# Battery_Protection_Board.net
KiCad netlist of a schematic drawn in EAGLE
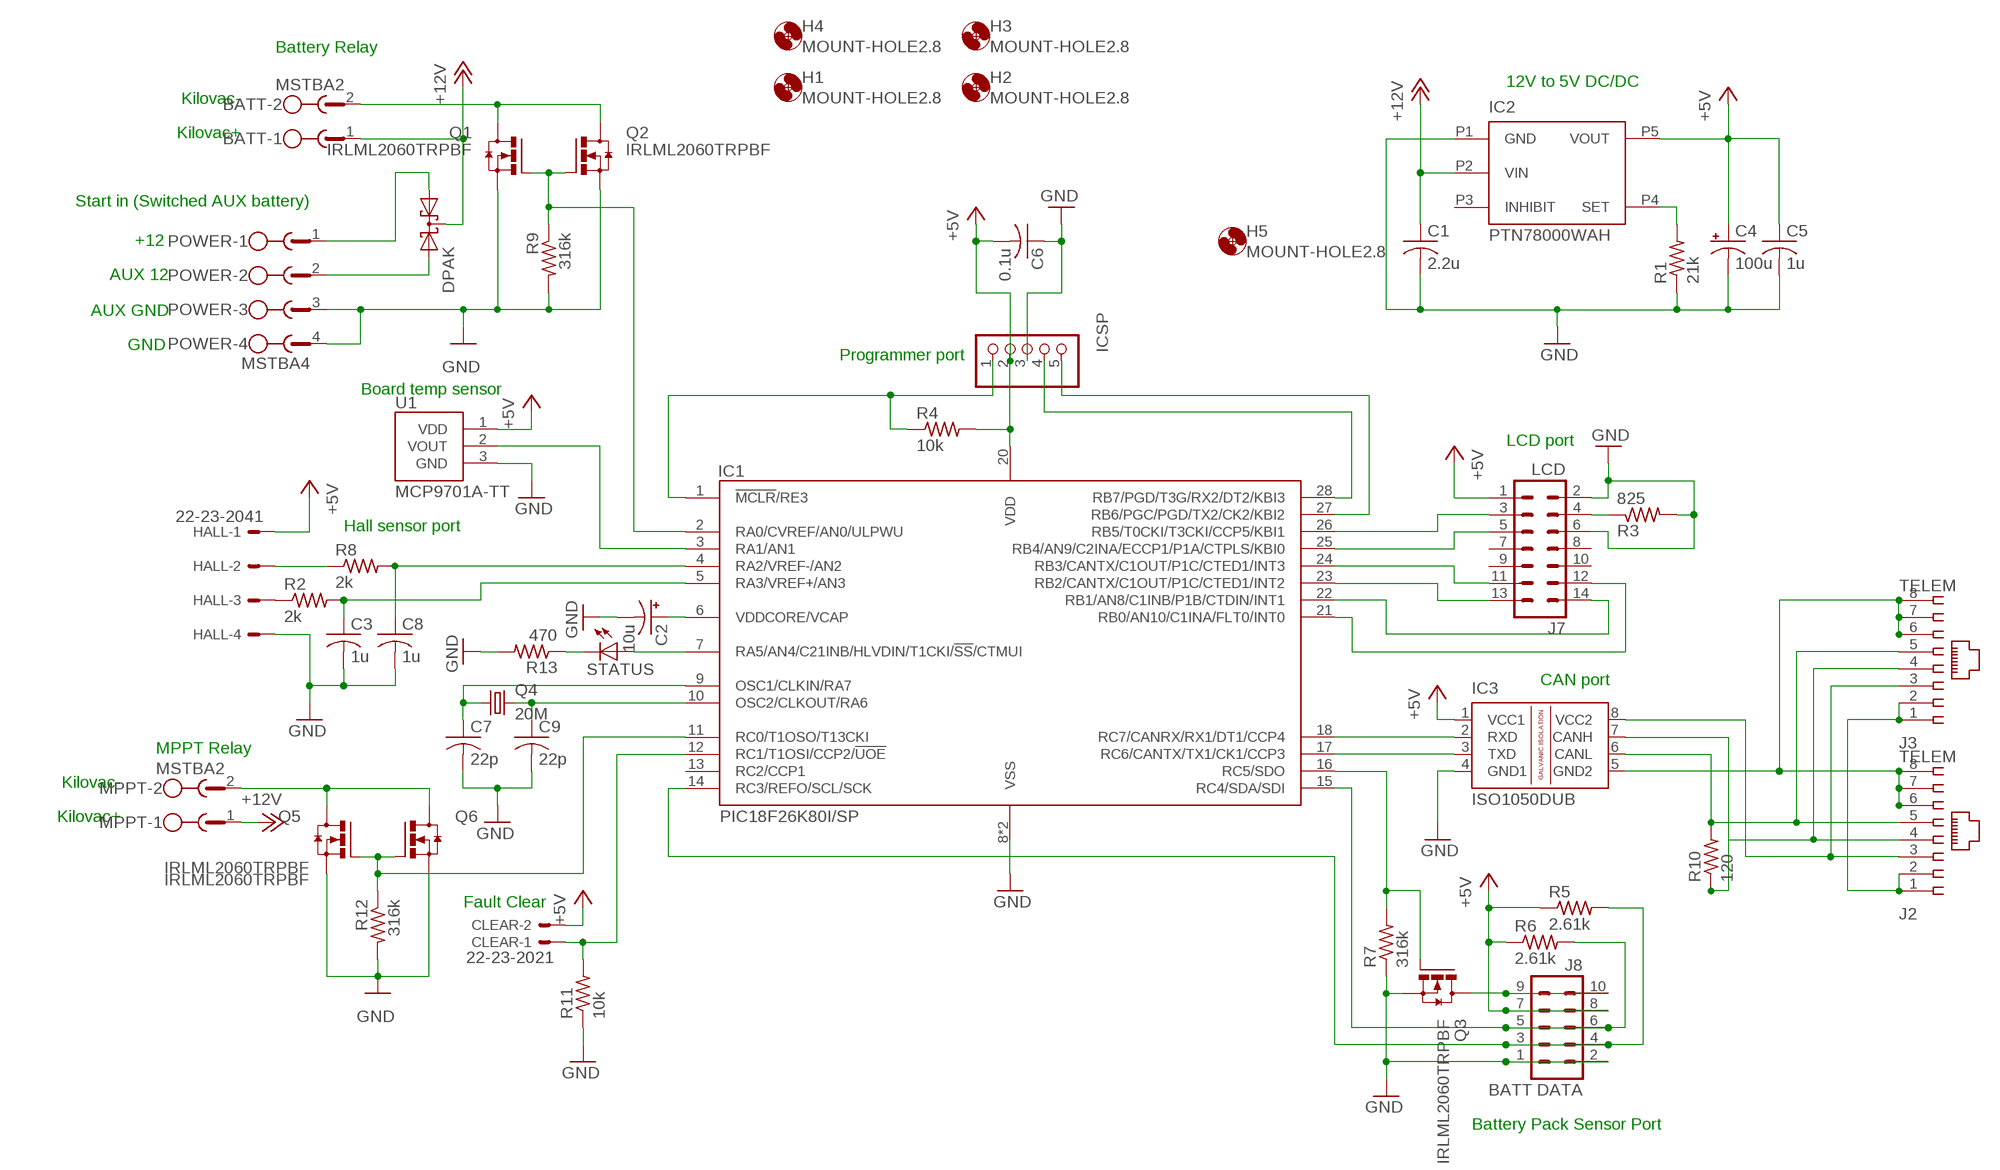
[diagram p0: schematic, sheet 1]

(export (version "E")
  (design (tool "Eeschema 10.0.6"))
  (components
    (comp (ref "BATT")
      (value "MSTBA2")
      (footprint "eagle-import:MSTBA2")
      (fields (field (name "MF") "FARNELL") (field (name "MPN") "1757242"))
      (libsource (lib "eagle-import") (part "MSTBA2"))
    )
    (comp (ref "C1")
      (value "2.2u")
      (footprint "eagle-import:C1206")
      (libsource (lib "eagle-import") (part "C-USC1206"))
    )
    (comp (ref "C2")
      (value "10u")
      (footprint "eagle-import:TT2D4")
      (libsource (lib "eagle-import") (part "CPOL-USTT2D4"))
    )
    (comp (ref "C3")
      (value "1u")
      (footprint "eagle-import:C0805")
      (libsource (lib "eagle-import") (part "C-USC0805"))
    )
    (comp (ref "C4")
      (value "100u")
      (footprint "eagle-import:SMC_D")
      (libsource (lib "eagle-import") (part "CPOL-USSMCD"))
    )
    (comp (ref "C5")
      (value "1u")
      (footprint "eagle-import:C0805")
      (libsource (lib "eagle-import") (part "C-USC0805"))
    )
    (comp (ref "C6")
      (value "0.1u")
      (footprint "eagle-import:C0805")
      (libsource (lib "eagle-import") (part "C-USC0805"))
    )
    (comp (ref "C7")
      (value "22p")
      (footprint "eagle-import:C0805")
      (libsource (lib "eagle-import") (part "C-USC0805"))
    )
    (comp (ref "C8")
      (value "1u")
      (footprint "eagle-import:C0805")
      (libsource (lib "eagle-import") (part "C-USC0805"))
    )
    (comp (ref "C9")
      (value "22p")
      (footprint "eagle-import:C0805")
      (libsource (lib "eagle-import") (part "C-USC0805"))
    )
    (comp (ref "CLEAR")
      (value "22-23-2021")
      (footprint "eagle-import:22-23-2021")
      (fields (field (name "MF") "MOLEX"))
      (libsource (lib "eagle-import") (part "22-23-2021"))
    )
    (comp (ref "DPAK")
      (value "DIODE_2SCHOTTKY-DPAK")
      (footprint "eagle-import:DPAK")
      (libsource (lib "eagle-import") (part "DIODE_2SCHOTTKY-DPAK"))
    )
    (comp (ref "H1")
      (value "MOUNT-HOLE2.8")
      (footprint "eagle-import:2,8")
      (libsource (lib "eagle-import") (part "MOUNT-HOLE2.8"))
    )
    (comp (ref "H2")
      (value "MOUNT-HOLE2.8")
      (footprint "eagle-import:2,8")
      (libsource (lib "eagle-import") (part "MOUNT-HOLE2.8"))
    )
    (comp (ref "H3")
      (value "MOUNT-HOLE2.8")
      (footprint "eagle-import:2,8")
      (libsource (lib "eagle-import") (part "MOUNT-HOLE2.8"))
    )
    (comp (ref "H4")
      (value "MOUNT-HOLE2.8")
      (footprint "eagle-import:2,8")
      (libsource (lib "eagle-import") (part "MOUNT-HOLE2.8"))
    )
    (comp (ref "H5")
      (value "MOUNT-HOLE2.8")
      (footprint "eagle-import:2,8")
      (libsource (lib "eagle-import") (part "MOUNT-HOLE2.8"))
    )
    (comp (ref "HALL")
      (value "22-23-2041")
      (footprint "eagle-import:22-23-2041")
      (fields (field (name "MF") "MOLEX"))
      (libsource (lib "eagle-import") (part "22-23-2041"))
    )
    (comp (ref "IC1")
      (value "PIC18F26K80I/SP")
      (footprint "eagle-import:DIL28_3")
      (libsource (lib "eagle-import") (part "PIC18F26K80I/SP"))
    )
    (comp (ref "IC2")
      (value "PTN78000WAH")
      (footprint "eagle-import:PTN78000")
      (libsource (lib "eagle-import") (part "PTN78000WAH"))
    )
    (comp (ref "IC3")
      (value "ISO1050DUB")
      (footprint "eagle-import:DUB-R-PDSO-G8")
      (fields (field (name "MPN") "ISO1050DUBR"))
      (libsource (lib "eagle-import") (part "ISO1050DUB"))
    )
    (comp (ref "ICSP")
      (value "ICD")
      (footprint "eagle-import:1X05")
      (libsource (lib "eagle-import") (part "PINHD-1X5"))
    )
    (comp (ref "J2")
      (value "TELEM")
      (footprint "eagle-import:215877-7")
      (libsource (lib "eagle-import") (part "215877-7"))
    )
    (comp (ref "J3")
      (value "TELEM")
      (footprint "eagle-import:215877-7")
      (libsource (lib "eagle-import") (part "215877-7"))
    )
    (comp (ref "J7")
      (value "LCD")
      (footprint "eagle-import:ML14")
      (libsource (lib "eagle-import") (part "ML14"))
    )
    (comp (ref "J8")
      (value "BATT DATA")
      (footprint "eagle-import:ML10")
      (libsource (lib "eagle-import") (part "ML10"))
    )
    (comp (ref "MPPT")
      (value "MSTBA2")
      (footprint "eagle-import:MSTBA2")
      (fields (field (name "MF") "FARNELL") (field (name "MPN") "1757242"))
      (libsource (lib "eagle-import") (part "MSTBA2"))
    )
    (comp (ref "POWER")
      (value "MSTBA4")
      (footprint "eagle-import:MSTBA4")
      (fields (field (name "MF") "FARNELL") (field (name "MPN") "1757268"))
      (libsource (lib "eagle-import") (part "MSTBA4"))
    )
    (comp (ref "Q1")
      (value "IRLML2060TRPBF")
      (footprint "eagle-import:SOT23")
      (libsource (lib "eagle-import") (part "IRLML2060TRPBF"))
    )
    (comp (ref "Q2")
      (value "IRLML2060TRPBF")
      (footprint "eagle-import:SOT23")
      (libsource (lib "eagle-import") (part "IRLML2060TRPBF"))
    )
    (comp (ref "Q3")
      (value "IRLML2060TRPBF")
      (footprint "eagle-import:SOT23")
      (libsource (lib "eagle-import") (part "IRLML2060TRPBF"))
    )
    (comp (ref "Q4")
      (value "20M")
      (footprint "eagle-import:HC49_S")
      (libsource (lib "eagle-import") (part "CRYSTALHC49S"))
    )
    (comp (ref "Q5")
      (value "IRLML2060TRPBF")
      (footprint "eagle-import:SOT23")
      (libsource (lib "eagle-import") (part "IRLML2060TRPBF"))
    )
    (comp (ref "Q6")
      (value "IRLML2060TRPBF")
      (footprint "eagle-import:SOT23")
      (libsource (lib "eagle-import") (part "IRLML2060TRPBF"))
    )
    (comp (ref "R1")
      (value "21k")
      (footprint "eagle-import:R0805")
      (libsource (lib "eagle-import") (part "rcl_R-US_R0805"))
    )
    (comp (ref "R2")
      (value "2k")
      (footprint "eagle-import:R0805")
      (libsource (lib "eagle-import") (part "rcl_R-US_R0805"))
    )
    (comp (ref "R3")
      (value "825")
      (footprint "eagle-import:R0805")
      (libsource (lib "eagle-import") (part "rcl_R-US_R0805"))
    )
    (comp (ref "R4")
      (value "10k")
      (footprint "eagle-import:R0805")
      (libsource (lib "eagle-import") (part "rcl_R-US_R0805"))
    )
    (comp (ref "R5")
      (value "2.61k")
      (footprint "eagle-import:R0805")
      (libsource (lib "eagle-import") (part "rcl_R-US_R0805"))
    )
    (comp (ref "R6")
      (value "2.61k")
      (footprint "eagle-import:R0805")
      (libsource (lib "eagle-import") (part "rcl_R-US_R0805"))
    )
    (comp (ref "R7")
      (value "316k")
      (footprint "eagle-import:R0805")
      (libsource (lib "eagle-import") (part "rcl_R-US_R0805"))
    )
    (comp (ref "R8")
      (value "2k")
      (footprint "eagle-import:R0805")
      (libsource (lib "eagle-import") (part "rcl_R-US_R0805"))
    )
    (comp (ref "R9")
      (value "316k")
      (footprint "eagle-import:R0805")
      (libsource (lib "eagle-import") (part "rcl_R-US_R0805"))
    )
    (comp (ref "R10")
      (value "120")
      (footprint "eagle-import:0207_7")
      (libsource (lib "eagle-import") (part "R-US_0207/7"))
    )
    (comp (ref "R11")
      (value "10k")
      (footprint "eagle-import:R0805")
      (libsource (lib "eagle-import") (part "rcl_R-US_R0805"))
    )
    (comp (ref "R12")
      (value "316k")
      (footprint "eagle-import:R0805")
      (libsource (lib "eagle-import") (part "rcl_R-US_R0805"))
    )
    (comp (ref "R13")
      (value "470")
      (footprint "eagle-import:R0805")
      (libsource (lib "eagle-import") (part "rcl_R-US_R0805"))
    )
    (comp (ref "STATUS")
      (value "LED5MM")
      (footprint "eagle-import:LED5MM")
      (libsource (lib "eagle-import") (part "LED5MM"))
    )
    (comp (ref "U1")
      (value "MCP9701A-TT")
      (footprint "eagle-import:SOT23")
      (libsource (lib "eagle-import") (part "MCP9701A-TT"))
    )
  )
  (nets
    (net (code "1") (name "+5V") (class "Default")
      (node (ref "C4") (pin "+") (pinfunction "+_+") (pintype "passive"))
      (node (ref "C5") (pin "1") (pinfunction "1_1") (pintype "passive"))
      (node (ref "C6") (pin "2") (pinfunction "2_2") (pintype "passive"))
      (node (ref "CLEAR") (pin "2") (pinfunction "S_2") (pintype "passive"))
      (node (ref "HALL") (pin "1") (pinfunction "S_1") (pintype "passive"))
      (node (ref "IC1") (pin "20") (pinfunction "VDD_20") (pintype "power_in"))
      (node (ref "IC2") (pin "P5") (pinfunction "VOUT_P5") (pintype "power_in"))
      (node (ref "IC3") (pin "1") (pinfunction "VCC1_1") (pintype "input"))
      (node (ref "ICSP") (pin "2") (pinfunction "2_2") (pintype "passive"))
      (node (ref "J7") (pin "1") (pinfunction "1_1") (pintype "passive"))
      (node (ref "J8") (pin "7") (pinfunction "7_7") (pintype "passive"))
      (node (ref "J8") (pin "8") (pinfunction "8_8") (pintype "passive"))
      (node (ref "R4") (pin "2") (pinfunction "2_2") (pintype "passive"))
      (node (ref "R5") (pin "1") (pinfunction "1_1") (pintype "passive"))
      (node (ref "R6") (pin "1") (pinfunction "1_1") (pintype "passive"))
      (node (ref "U1") (pin "1") (pinfunction "VDD_1") (pintype "power_in"))
    )
    (net (code "2") (name "+12V") (class "Default")
      (node (ref "BATT") (pin "1") (pinfunction "1_1") (pintype "passive"))
      (node (ref "C1") (pin "1") (pinfunction "1_1") (pintype "passive"))
      (node (ref "DPAK") (pin "3") (pinfunction "C_3") (pintype "passive"))
      (node (ref "IC2") (pin "P2") (pinfunction "VIN_P2") (pintype "power_in"))
      (node (ref "MPPT") (pin "1") (pinfunction "1_1") (pintype "passive"))
    )
    (net (code "3") (name "GND") (class "Default")
      (node (ref "C1") (pin "2") (pinfunction "2_2") (pintype "passive"))
      (node (ref "C2") (pin "-") (pinfunction "-_-") (pintype "passive"))
      (node (ref "C3") (pin "2") (pinfunction "2_2") (pintype "passive"))
      (node (ref "C4") (pin "-") (pinfunction "-_-") (pintype "passive"))
      (node (ref "C5") (pin "2") (pinfunction "2_2") (pintype "passive"))
      (node (ref "C6") (pin "1") (pinfunction "1_1") (pintype "passive"))
      (node (ref "C7") (pin "2") (pinfunction "2_2") (pintype "passive"))
      (node (ref "C8") (pin "2") (pinfunction "2_2") (pintype "passive"))
      (node (ref "C9") (pin "2") (pinfunction "2_2") (pintype "passive"))
      (node (ref "HALL") (pin "4") (pinfunction "S_4") (pintype "passive"))
      (node (ref "IC1") (pin "19") (pinfunction "VSS_19") (pintype "power_in"))
      (node (ref "IC1") (pin "8") (pinfunction "VSS_8") (pintype "power_in"))
      (node (ref "IC2") (pin "P1") (pinfunction "GND_P1") (pintype "power_in"))
      (node (ref "IC3") (pin "4") (pinfunction "GND1_4") (pintype "input"))
      (node (ref "ICSP") (pin "3") (pinfunction "3_3") (pintype "passive"))
      (node (ref "J7") (pin "2") (pinfunction "2_2") (pintype "passive"))
      (node (ref "J7") (pin "6") (pinfunction "6_6") (pintype "passive"))
      (node (ref "J8") (pin "1") (pinfunction "1_1") (pintype "passive"))
      (node (ref "J8") (pin "2") (pinfunction "2_2") (pintype "passive"))
      (node (ref "POWER") (pin "3") (pinfunction "1_3") (pintype "passive"))
      (node (ref "POWER") (pin "4") (pinfunction "1_4") (pintype "passive"))
      (node (ref "Q1") (pin "2") (pinfunction "S_2") (pintype "passive"))
      (node (ref "Q2") (pin "2") (pinfunction "S_2") (pintype "passive"))
      (node (ref "Q3") (pin "2") (pinfunction "S_2") (pintype "passive"))
      (node (ref "Q5") (pin "2") (pinfunction "S_2") (pintype "passive"))
      (node (ref "Q6") (pin "2") (pinfunction "S_2") (pintype "passive"))
      (node (ref "R1") (pin "1") (pinfunction "1_1") (pintype "passive"))
      (node (ref "R11") (pin "1") (pinfunction "1_1") (pintype "passive"))
      (node (ref "R12") (pin "2") (pinfunction "2_2") (pintype "passive"))
      (node (ref "R13") (pin "2") (pinfunction "2_2") (pintype "passive"))
      (node (ref "R3") (pin "2") (pinfunction "2_2") (pintype "passive"))
      (node (ref "R7") (pin "1") (pinfunction "1_1") (pintype "passive"))
      (node (ref "R9") (pin "2") (pinfunction "2_2") (pintype "passive"))
      (node (ref "U1") (pin "3") (pinfunction "GND_3") (pintype "power_in"))
    )
    (net (code "4") (name "Net-(BATTB-1)") (class "Default")
      (node (ref "BATT") (pin "2") (pinfunction "1_2") (pintype "passive"))
      (node (ref "Q1") (pin "3") (pinfunction "D_3") (pintype "passive"))
      (node (ref "Q2") (pin "3") (pinfunction "D_3") (pintype "passive"))
    )
    (net (code "5") (name "Net-(CLEARA-S)") (class "Default")
      (node (ref "CLEAR") (pin "1") (pinfunction "S_1") (pintype "passive"))
      (node (ref "IC1") (pin "12") (pinfunction "RC1/T1OSI/CCP2/~{UOE}_12") (pintype "bidirectional"))
      (node (ref "R11") (pin "2") (pinfunction "2_2") (pintype "passive"))
    )
    (net (code "6") (name "Net-(DPAK-A1)") (class "Default")
      (node (ref "DPAK") (pin "1") (pinfunction "A1_1") (pintype "passive"))
      (node (ref "POWER") (pin "1") (pinfunction "1_1") (pintype "passive"))
    )
    (net (code "7") (name "Net-(DPAK-A2)") (class "Default")
      (node (ref "DPAK") (pin "2") (pinfunction "A2_2") (pintype "passive"))
      (node (ref "POWER") (pin "2") (pinfunction "1_2") (pintype "passive"))
    )
    (net (code "8") (name "Net-(HALLB-S)") (class "Default")
      (node (ref "HALL") (pin "2") (pinfunction "S_2") (pintype "passive"))
      (node (ref "R8") (pin "1") (pinfunction "1_1") (pintype "passive"))
    )
    (net (code "9") (name "Net-(HALLC-S)") (class "Default")
      (node (ref "HALL") (pin "3") (pinfunction "S_3") (pintype "passive"))
      (node (ref "R2") (pin "1") (pinfunction "1_1") (pintype "passive"))
    )
    (net (code "10") (name "Net-(IC1-OSC1{slash}CLKIN{slash}RA7)") (class "Default")
      (node (ref "C7") (pin "1") (pinfunction "1_1") (pintype "passive"))
      (node (ref "IC1") (pin "9") (pinfunction "OSC1/CLKIN/RA7_9") (pintype "bidirectional"))
      (node (ref "Q4") (pin "1") (pinfunction "1_1") (pintype "passive"))
    )
    (net (code "11") (name "Net-(IC1-OSC2{slash}CLKOUT{slash}RA6)") (class "Default")
      (node (ref "C9") (pin "1") (pinfunction "1_1") (pintype "passive"))
      (node (ref "IC1") (pin "10") (pinfunction "OSC2/CLKOUT/RA6_10") (pintype "bidirectional"))
      (node (ref "Q4") (pin "2") (pinfunction "2_2") (pintype "passive"))
    )
    (net (code "12") (name "Net-(IC1-RA0{slash}CVREF{slash}AN0{slash}ULPWU)") (class "Default")
      (node (ref "IC1") (pin "2") (pinfunction "RA0/CVREF/AN0/ULPWU_2") (pintype "bidirectional"))
      (node (ref "Q1") (pin "1") (pinfunction "G_1") (pintype "passive"))
      (node (ref "Q2") (pin "1") (pinfunction "G_1") (pintype "passive"))
      (node (ref "R9") (pin "1") (pinfunction "1_1") (pintype "passive"))
    )
    (net (code "13") (name "Net-(IC1-RA1{slash}AN1)") (class "Default")
      (node (ref "IC1") (pin "3") (pinfunction "RA1/AN1_3") (pintype "bidirectional"))
      (node (ref "U1") (pin "2") (pinfunction "VOUT_2") (pintype "output"))
    )
    (net (code "14") (name "Net-(IC1-RA2{slash}VREF-{slash}AN2)") (class "Default")
      (node (ref "C8") (pin "1") (pinfunction "1_1") (pintype "passive"))
      (node (ref "IC1") (pin "4") (pinfunction "RA2/VREF-/AN2_4") (pintype "bidirectional"))
      (node (ref "R8") (pin "2") (pinfunction "2_2") (pintype "passive"))
    )
    (net (code "15") (name "Net-(IC1-RA3{slash}VREF+{slash}AN3)") (class "Default")
      (node (ref "C3") (pin "1") (pinfunction "1_1") (pintype "passive"))
      (node (ref "IC1") (pin "5") (pinfunction "RA3/VREF+/AN3_5") (pintype "bidirectional"))
      (node (ref "R2") (pin "2") (pinfunction "2_2") (pintype "passive"))
    )
    (net (code "16") (name "Net-(IC1-RA5{slash}AN4{slash}C21INB{slash}HLVDIN{slash}T1CKI{slash}~{SS}{slash}CTMUI)") (class "Default")
      (node (ref "IC1") (pin "7") (pinfunction "RA5/AN4/C21INB/HLVDIN/T1CKI/~{SS}/CTMUI_7") (pintype "bidirectional"))
      (node (ref "STATUS") (pin "A") (pinfunction "A_A") (pintype "passive"))
    )
    (net (code "17") (name "Net-(IC1-RB0{slash}AN10{slash}C1INA{slash}FLT0{slash}INT0)") (class "Default")
      (node (ref "IC1") (pin "21") (pinfunction "RB0/AN10/C1INA/FLT0/INT0_21") (pintype "bidirectional"))
      (node (ref "J7") (pin "12") (pinfunction "12_12") (pintype "passive"))
    )
    (net (code "18") (name "Net-(IC1-RB1{slash}AN8{slash}C1INB{slash}P1B{slash}CTDIN{slash}INT1)") (class "Default")
      (node (ref "IC1") (pin "22") (pinfunction "RB1/AN8/C1INB/P1B/CTDIN/INT1_22") (pintype "bidirectional"))
      (node (ref "J7") (pin "14") (pinfunction "14_14") (pintype "passive"))
    )
    (net (code "19") (name "Net-(IC1-RB2{slash}CANTX{slash}C1OUT{slash}P1C{slash}CTED1{slash}INT2)") (class "Default")
      (node (ref "IC1") (pin "23") (pinfunction "RB2/CANTX/C1OUT/P1C/CTED1/INT2_23") (pintype "bidirectional"))
      (node (ref "J7") (pin "13") (pinfunction "13_13") (pintype "passive"))
    )
    (net (code "20") (name "Net-(IC1-RB3{slash}CANTX{slash}C1OUT{slash}P1C{slash}CTED1{slash}INT3)") (class "Default")
      (node (ref "IC1") (pin "24") (pinfunction "RB3/CANTX/C1OUT/P1C/CTED1/INT3_24") (pintype "bidirectional"))
      (node (ref "J7") (pin "11") (pinfunction "11_11") (pintype "passive"))
    )
    (net (code "21") (name "Net-(IC1-RB4{slash}AN9{slash}C2INA{slash}ECCP1{slash}P1A{slash}CTPLS{slash}KBI0)") (class "Default")
      (node (ref "IC1") (pin "25") (pinfunction "RB4/AN9/C2INA/ECCP1/P1A/CTPLS/KBI0_25") (pintype "bidirectional"))
      (node (ref "J7") (pin "5") (pinfunction "5_5") (pintype "passive"))
    )
    (net (code "22") (name "Net-(IC1-RB5{slash}T0CKI{slash}T3CKI{slash}CCP5{slash}KBI1)") (class "Default")
      (node (ref "IC1") (pin "26") (pinfunction "RB5/T0CKI/T3CKI/CCP5/KBI1_26") (pintype "bidirectional"))
      (node (ref "J7") (pin "3") (pinfunction "3_3") (pintype "passive"))
    )
    (net (code "23") (name "Net-(IC1-RB6{slash}PGC{slash}PGD{slash}TX2{slash}CK2{slash}KBI2)") (class "Default")
      (node (ref "IC1") (pin "27") (pinfunction "RB6/PGC/PGD/TX2/CK2/KBI2_27") (pintype "bidirectional"))
      (node (ref "ICSP") (pin "5") (pinfunction "5_5") (pintype "passive"))
    )
    (net (code "24") (name "Net-(IC1-RB7{slash}PGD{slash}T3G{slash}RX2{slash}DT2{slash}KBI3)") (class "Default")
      (node (ref "IC1") (pin "28") (pinfunction "RB7/PGD/T3G/RX2/DT2/KBI3_28") (pintype "bidirectional"))
      (node (ref "ICSP") (pin "4") (pinfunction "4_4") (pintype "passive"))
    )
    (net (code "25") (name "Net-(IC1-RC0{slash}T1OSO{slash}T13CKI)") (class "Default")
      (node (ref "IC1") (pin "11") (pinfunction "RC0/T1OSO/T13CKI_11") (pintype "bidirectional"))
      (node (ref "Q5") (pin "1") (pinfunction "G_1") (pintype "passive"))
      (node (ref "Q6") (pin "1") (pinfunction "G_1") (pintype "passive"))
      (node (ref "R12") (pin "1") (pinfunction "1_1") (pintype "passive"))
    )
    (net (code "26") (name "Net-(IC1-RC3{slash}REFO{slash}SCL{slash}SCK)") (class "Default")
      (node (ref "IC1") (pin "14") (pinfunction "RC3/REFO/SCL/SCK_14") (pintype "bidirectional"))
      (node (ref "J8") (pin "3") (pinfunction "3_3") (pintype "passive"))
      (node (ref "J8") (pin "4") (pinfunction "4_4") (pintype "passive"))
      (node (ref "R5") (pin "2") (pinfunction "2_2") (pintype "passive"))
    )
    (net (code "27") (name "Net-(IC1-RC4{slash}SDA{slash}SDI)") (class "Default")
      (node (ref "IC1") (pin "15") (pinfunction "RC4/SDA/SDI_15") (pintype "bidirectional"))
      (node (ref "J8") (pin "5") (pinfunction "5_5") (pintype "passive"))
      (node (ref "J8") (pin "6") (pinfunction "6_6") (pintype "passive"))
      (node (ref "R6") (pin "2") (pinfunction "2_2") (pintype "passive"))
    )
    (net (code "28") (name "Net-(IC1-RC5{slash}SDO)") (class "Default")
      (node (ref "IC1") (pin "16") (pinfunction "RC5/SDO_16") (pintype "bidirectional"))
      (node (ref "Q3") (pin "1") (pinfunction "G_1") (pintype "passive"))
      (node (ref "R7") (pin "2") (pinfunction "2_2") (pintype "passive"))
    )
    (net (code "29") (name "Net-(IC1-RC6{slash}CANTX{slash}TX1{slash}CK1{slash}CCP3)") (class "Default")
      (node (ref "IC1") (pin "17") (pinfunction "RC6/CANTX/TX1/CK1/CCP3_17") (pintype "bidirectional"))
      (node (ref "IC3") (pin "3") (pinfunction "TXD_3") (pintype "input"))
    )
    (net (code "30") (name "Net-(IC1-RC7{slash}CANRX{slash}RX1{slash}DT1{slash}CCP4)") (class "Default")
      (node (ref "IC1") (pin "18") (pinfunction "RC7/CANRX/RX1/DT1/CCP4_18") (pintype "bidirectional"))
      (node (ref "IC3") (pin "2") (pinfunction "RXD_2") (pintype "input"))
    )
    (net (code "31") (name "Net-(IC1-VDDCORE{slash}VCAP)") (class "Default")
      (node (ref "C2") (pin "+") (pinfunction "+_+") (pintype "passive"))
      (node (ref "IC1") (pin "6") (pinfunction "VDDCORE/VCAP_6") (pintype "bidirectional"))
    )
    (net (code "32") (name "Net-(IC1-~{MCLR}{slash}RE3)") (class "Default")
      (node (ref "IC1") (pin "1") (pinfunction "~{MCLR}/RE3_1") (pintype "input"))
      (node (ref "ICSP") (pin "1") (pinfunction "1_1") (pintype "passive"))
      (node (ref "R4") (pin "1") (pinfunction "1_1") (pintype "passive"))
    )
    (net (code "33") (name "Net-(IC2-SET)") (class "Default")
      (node (ref "IC2") (pin "P4") (pinfunction "SET_P4") (pintype "bidirectional"))
      (node (ref "R1") (pin "2") (pinfunction "2_2") (pintype "passive"))
    )
    (net (code "34") (name "Net-(IC3-CANH)") (class "Default")
      (node (ref "IC3") (pin "7") (pinfunction "CANH_7") (pintype "input"))
      (node (ref "J2") (pin "4") (pinfunction "4_4") (pintype "passive"))
      (node (ref "J3") (pin "4") (pinfunction "4_4") (pintype "passive"))
      (node (ref "R10") (pin "1") (pinfunction "1_1") (pintype "passive"))
    )
    (net (code "35") (name "Net-(IC3-CANL)") (class "Default")
      (node (ref "IC3") (pin "6") (pinfunction "CANL_6") (pintype "input"))
      (node (ref "J2") (pin "5") (pinfunction "5_5") (pintype "passive"))
      (node (ref "J3") (pin "5") (pinfunction "5_5") (pintype "passive"))
      (node (ref "R10") (pin "2") (pinfunction "2_2") (pintype "passive"))
    )
    (net (code "36") (name "Net-(IC3-GND2)") (class "Default")
      (node (ref "IC3") (pin "5") (pinfunction "GND2_5") (pintype "input"))
      (node (ref "J2") (pin "6") (pinfunction "6_6") (pintype "passive"))
      (node (ref "J2") (pin "7") (pinfunction "7_7") (pintype "passive"))
      (node (ref "J2") (pin "8") (pinfunction "8_8") (pintype "passive"))
      (node (ref "J3") (pin "6") (pinfunction "6_6") (pintype "passive"))
      (node (ref "J3") (pin "7") (pinfunction "7_7") (pintype "passive"))
      (node (ref "J3") (pin "8") (pinfunction "8_8") (pintype "passive"))
    )
    (net (code "37") (name "Net-(IC3-VCC2)") (class "Default")
      (node (ref "IC3") (pin "8") (pinfunction "VCC2_8") (pintype "input"))
      (node (ref "J2") (pin "3") (pinfunction "3_3") (pintype "passive"))
      (node (ref "J3") (pin "3") (pinfunction "3_3") (pintype "passive"))
    )
    (net (code "38") (name "Net-(J2-Pad1)") (class "Default")
      (node (ref "J2") (pin "1") (pinfunction "1_1") (pintype "passive"))
      (node (ref "J2") (pin "2") (pinfunction "2_2") (pintype "passive"))
      (node (ref "J3") (pin "1") (pinfunction "1_1") (pintype "passive"))
      (node (ref "J3") (pin "2") (pinfunction "2_2") (pintype "passive"))
    )
    (net (code "39") (name "Net-(J7-Pad4)") (class "Default")
      (node (ref "J7") (pin "4") (pinfunction "4_4") (pintype "passive"))
      (node (ref "R3") (pin "1") (pinfunction "1_1") (pintype "passive"))
    )
    (net (code "40") (name "Net-(MPPTB-1)") (class "Default")
      (node (ref "MPPT") (pin "2") (pinfunction "1_2") (pintype "passive"))
      (node (ref "Q5") (pin "3") (pinfunction "D_3") (pintype "passive"))
      (node (ref "Q6") (pin "3") (pinfunction "D_3") (pintype "passive"))
    )
    (net (code "41") (name "Net-(Q3-D)") (class "Default")
      (node (ref "J8") (pin "10") (pinfunction "10_10") (pintype "passive"))
      (node (ref "J8") (pin "9") (pinfunction "9_9") (pintype "passive"))
      (node (ref "Q3") (pin "3") (pinfunction "D_3") (pintype "passive"))
    )
    (net (code "42") (name "Net-(STATUS-C)") (class "Default")
      (node (ref "R13") (pin "1") (pinfunction "1_1") (pintype "passive"))
      (node (ref "STATUS") (pin "K") (pinfunction "C_K") (pintype "passive"))
    )
    (net (code "43") (name "unconnected-(IC1-RC2{slash}CCP1-Pad13)") (class "Default")
      (node (ref "IC1") (pin "13") (pinfunction "RC2/CCP1_13") (pintype "bidirectional"))
    )
    (net (code "44") (name "unconnected-(IC2-INHIBIT-PadP3)") (class "Default")
      (node (ref "IC2") (pin "P3") (pinfunction "INHIBIT_P3") (pintype "bidirectional"))
    )
    (net (code "45") (name "unconnected-(J7-Pad7)") (class "Default")
      (node (ref "J7") (pin "7") (pinfunction "7_7") (pintype "passive"))
    )
    (net (code "46") (name "unconnected-(J7-Pad8)") (class "Default")
      (node (ref "J7") (pin "8") (pinfunction "8_8") (pintype "passive"))
    )
    (net (code "47") (name "unconnected-(J7-Pad9)") (class "Default")
      (node (ref "J7") (pin "9") (pinfunction "9_9") (pintype "passive"))
    )
    (net (code "48") (name "unconnected-(J7-Pad10)") (class "Default")
      (node (ref "J7") (pin "10") (pinfunction "10_10") (pintype "passive"))
    )
  )
)
